# MCU.net
KiCad netlist of a schematic drawn in Altium Designer
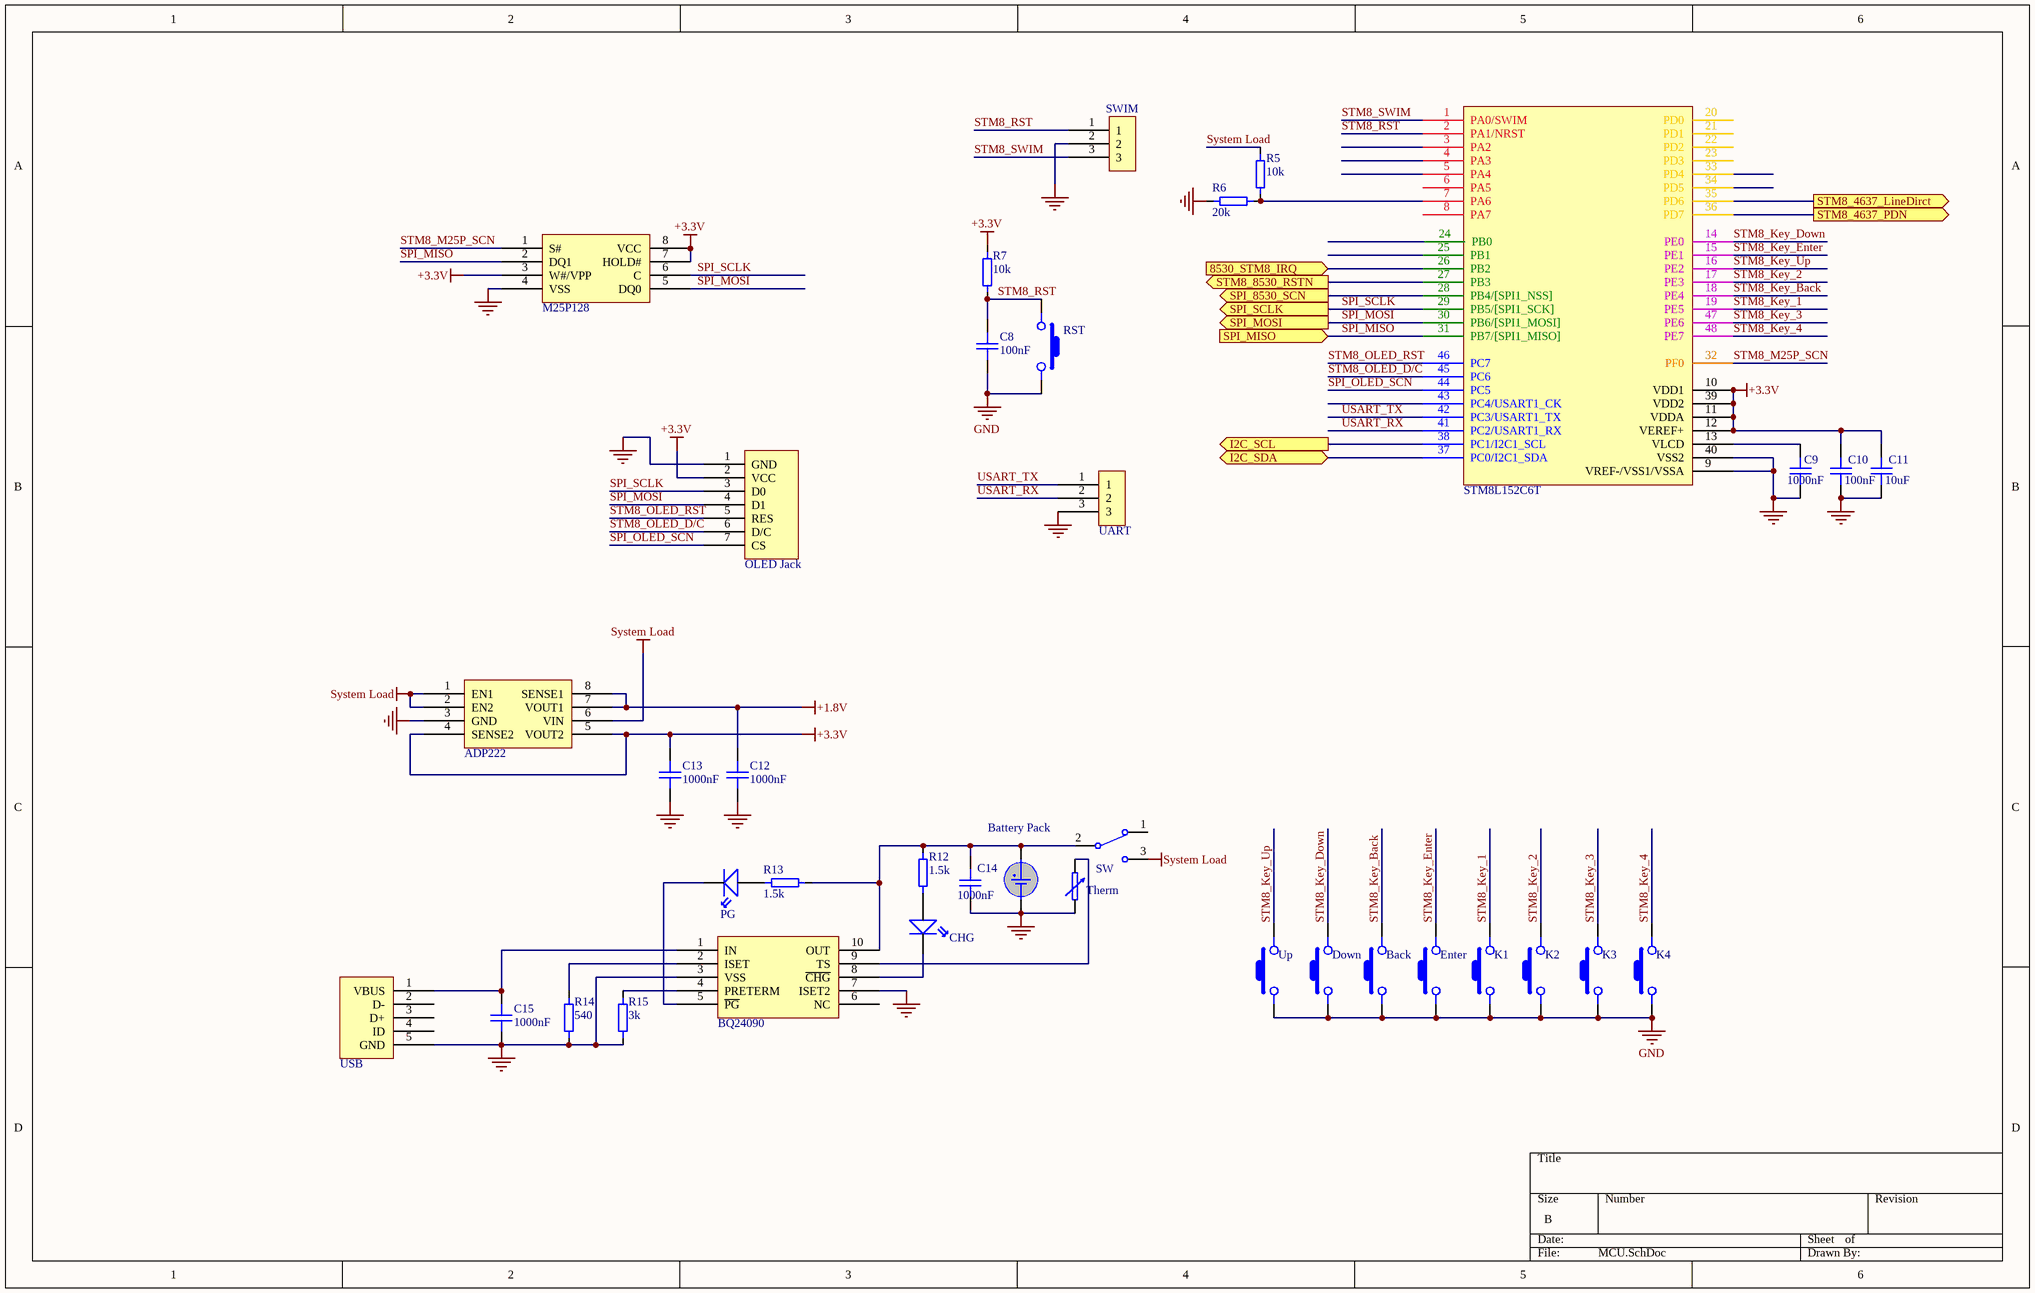
[diagram p0: MCU.SchDoc]

(export (version "E")
  (design (tool "Eeschema 10.0.6"))
  (components
    (comp (ref "ADP222")
      (value "ADP222ACPZ-1833-R7")
      (footprint "ADP22x")
      (libsource (lib "SuperLib") (part "ADP222"))
    )
    (comp (ref "Back") (value "Button") (footprint "Button_3x4") (libsource (lib "WPU161C") (part "Button")))
    (comp (ref "Battery Pack")
      (value "Battery Pack")
      (footprint "Battery Jack small")
      (libsource (lib "SuperLib") (part "Battery Pack"))
    )
    (comp (ref "BQ24090")
      (value "BQ24090")
      (footprint "BQ24090")
      (libsource (lib "WPU161C") (part "BQ24090"))
    )
    (comp (ref "C8")
      (value "100nF")
      (footprint "SMD 0402")
      (fields (field (name "Comment") "Capacity SMD"))
      (libsource (lib "WPU161C") (part "Capacity SMD"))
    )
    (comp (ref "C9")
      (value "1000nF")
      (footprint "SMD 0402")
      (fields (field (name "Comment") "Capacity SMD"))
      (libsource (lib "WPU161C") (part "Capacity SMD"))
    )
    (comp (ref "C10")
      (value "100nF")
      (footprint "SMD 0402")
      (fields (field (name "Comment") "Capacity SMD"))
      (libsource (lib "WPU161C") (part "Capacity SMD"))
    )
    (comp (ref "C11")
      (value "10uF")
      (footprint "SMD 0402")
      (fields (field (name "Comment") "Capacity SMD"))
      (libsource (lib "WPU161C") (part "Capacity SMD"))
    )
    (comp (ref "C12")
      (value "1000nF")
      (footprint "SMD 0402")
      (fields (field (name "Comment") "Capacity SMD"))
      (libsource (lib "WPU161C") (part "Capacity SMD"))
    )
    (comp (ref "C13")
      (value "1000nF")
      (footprint "SMD 0402")
      (fields (field (name "Comment") "Capacity SMD"))
      (libsource (lib "WPU161C") (part "Capacity SMD"))
    )
    (comp (ref "C14")
      (value "1000nF")
      (footprint "SMD 0402")
      (fields (field (name "Comment") "Capacity SMD"))
      (libsource (lib "WPU161C") (part "Capacity SMD"))
    )
    (comp (ref "C15")
      (value "1000nF")
      (footprint "SMD 0402_silk")
      (fields (field (name "Comment") "Capacity SMD"))
      (libsource (lib "WPU161C") (part "Capacity SMD"))
    )
    (comp (ref "CHG") (value "LED") (footprint "LED_0603") (libsource (lib "WPU161C") (part "LED")))
    (comp (ref "Down") (value "Button") (footprint "Button_3x4") (libsource (lib "WPU161C") (part "Button")))
    (comp (ref "Enter") (value "Button") (footprint "Button_3x4") (libsource (lib "WPU161C") (part "Button")))
    (comp (ref "K1") (value "Button") (footprint "Button_3x4") (libsource (lib "WPU161C") (part "Button")))
    (comp (ref "K2") (value "Button") (footprint "Button_3x4") (libsource (lib "WPU161C") (part "Button")))
    (comp (ref "K3") (value "Button") (footprint "Button_3x4") (libsource (lib "WPU161C") (part "Button")))
    (comp (ref "K4") (value "Button") (footprint "Button_3x4") (libsource (lib "WPU161C") (part "Button")))
    (comp (ref "M25P128")
      (value "M25P128")
      (footprint "M25P128")
      (libsource (lib "WPU161C") (part "M25P128"))
    )
    (comp (ref "OLED Jack")
      (value "OLED Jack")
      (footprint "OLED Jack")
      (libsource (lib "WPU161C") (part "OLED Jack"))
    )
    (comp (ref "PG") (value "LED") (footprint "LED_0603") (libsource (lib "WPU161C") (part "LED")))
    (comp (ref "R5")
      (value "10k")
      (footprint "SMD 0402")
      (fields (field (name "Comment") "Resistor SMD"))
      (libsource (lib "WPU161C") (part "Resistor SMD"))
    )
    (comp (ref "R6")
      (value "20k")
      (footprint "SMD 0402")
      (fields (field (name "Comment") "Resistor SMD"))
      (libsource (lib "WPU161C") (part "Resistor SMD"))
    )
    (comp (ref "R7")
      (value "10k")
      (footprint "SMD 0402")
      (fields (field (name "Comment") "Resistor SMD"))
      (libsource (lib "WPU161C") (part "Resistor SMD"))
    )
    (comp (ref "R12")
      (value "1.5k")
      (footprint "SMD 0402")
      (fields (field (name "Comment") "Resistor SMD"))
      (libsource (lib "WPU161C") (part "Resistor SMD"))
    )
    (comp (ref "R13")
      (value "1.5k")
      (footprint "SMD 0402")
      (fields (field (name "Comment") "Resistor SMD"))
      (libsource (lib "WPU161C") (part "Resistor SMD"))
    )
    (comp (ref "R14")
      (value "540")
      (footprint "SMD 0402")
      (fields (field (name "Comment") "Resistor SMD"))
      (libsource (lib "WPU161C") (part "Resistor SMD"))
    )
    (comp (ref "R15")
      (value "3k")
      (footprint "SMD 0402")
      (fields (field (name "Comment") "Resistor SMD"))
      (libsource (lib "WPU161C") (part "Resistor SMD"))
    )
    (comp (ref "RST") (value "Button") (footprint "Button_3x4") (libsource (lib "WPU161C") (part "Button")))
    (comp (ref "STM8L152C6T")
      (value "STM8L152C6T")
      (footprint "STM LQFP48")
      (libsource (lib "WPU161C") (part "STM8L152C6T"))
    )
    (comp (ref "SW") (value "Switch") (footprint "Switch 2P2T") (libsource (lib "WPU161C") (part "Switch")))
    (comp (ref "SWIM")
      (value "Header_3x1")
      (footprint "HEADER_3x1_2.54")
      (libsource (lib "WPU161C") (part "Header_3x1"))
    )
    (comp (ref "Therm")
      (value "Thermistor")
      (footprint "Header_2x1_2.00")
      (libsource (lib "WPU161C") (part "Thermistor NTC"))
    )
    (comp (ref "UART")
      (value "Header_3x1")
      (footprint "HEADER_3x1_2.54")
      (libsource (lib "WPU161C") (part "Header_3x1"))
    )
    (comp (ref "Up") (value "Button") (footprint "Button_3x4") (libsource (lib "WPU161C") (part "Button")))
    (comp (ref "USB")
      (value "USB Jack Mirco-B")
      (footprint "USB Micro-B")
      (libsource (lib "WPU161C") (part "USB Jack Micro-B"))
    )
  )
  (nets
    (net (code "1") (name "+1.8V") (class "Default")
      (node (ref "ADP222") (pin "7") (pinfunction "VOUT1_7") (pintype "passive"))
      (node (ref "ADP222") (pin "8") (pinfunction "SENSE1_8") (pintype "passive"))
      (node (ref "C12") (pin "1") (pintype "passive"))
    )
    (net (code "2") (name "+3.3V") (class "Default")
      (node (ref "ADP222") (pin "4") (pinfunction "SENSE2_4") (pintype "passive"))
      (node (ref "ADP222") (pin "5") (pinfunction "VOUT2_5") (pintype "passive"))
      (node (ref "C10") (pin "2") (pintype "passive"))
      (node (ref "C11") (pin "2") (pintype "passive"))
      (node (ref "C13") (pin "2") (pintype "passive"))
      (node (ref "M25P128") (pin "3") (pinfunction "W#/VPP_3") (pintype "passive"))
      (node (ref "M25P128") (pin "7") (pinfunction "HOLD#_7") (pintype "passive"))
      (node (ref "M25P128") (pin "8") (pinfunction "VCC_8") (pintype "passive"))
      (node (ref "OLED Jack") (pin "2") (pinfunction "VCC_2") (pintype "passive"))
      (node (ref "R7") (pin "2") (pintype "passive"))
      (node (ref "STM8L152C6T") (pin "10") (pinfunction "VDD1_10") (pintype "passive"))
      (node (ref "STM8L152C6T") (pin "11") (pinfunction "VDDA_11") (pintype "passive"))
      (node (ref "STM8L152C6T") (pin "12") (pinfunction "VEREF+_12") (pintype "passive"))
      (node (ref "STM8L152C6T") (pin "39") (pinfunction "VDD2_39") (pintype "passive"))
    )
    (net (code "3") (name "/8530_STM8_IRQ") (class "Default")
      (node (ref "STM8L152C6T") (pin "26") (pinfunction "PB2_26") (pintype "passive"))
    )
    (net (code "4") (name "/I2C_SCL") (class "Default")
      (node (ref "STM8L152C6T") (pin "38") (pinfunction "PC1/I2C1_SCL_38") (pintype "passive"))
    )
    (net (code "5") (name "/I2C_SDA") (class "Default")
      (node (ref "STM8L152C6T") (pin "37") (pinfunction "PC0/I2C1_SDA_37") (pintype "passive"))
    )
    (net (code "6") (name "/SPI_8530_SCN") (class "Default")
      (node (ref "STM8L152C6T") (pin "28") (pinfunction "PB4/[SPI1_NSS]_28") (pintype "passive"))
    )
    (net (code "7") (name "/SPI_MISO") (class "Default")
      (node (ref "M25P128") (pin "2") (pinfunction "DQ1_2") (pintype "passive"))
      (node (ref "STM8L152C6T") (pin "31") (pinfunction "PB7/[SPI1_MISO]_31") (pintype "passive"))
    )
    (net (code "8") (name "/SPI_MOSI") (class "Default")
      (node (ref "M25P128") (pin "5") (pinfunction "DQ0_5") (pintype "passive"))
      (node (ref "OLED Jack") (pin "4") (pinfunction "D1_4") (pintype "passive"))
      (node (ref "STM8L152C6T") (pin "30") (pinfunction "PB6/[SPI1_MOSI]_30") (pintype "passive"))
    )
    (net (code "9") (name "/SPI_OLED_SCN") (class "Default")
      (node (ref "OLED Jack") (pin "7") (pinfunction "CS_7") (pintype "passive"))
      (node (ref "STM8L152C6T") (pin "44") (pinfunction "PC5_44") (pintype "passive"))
    )
    (net (code "10") (name "/SPI_SCLK") (class "Default")
      (node (ref "M25P128") (pin "6") (pinfunction "C_6") (pintype "passive"))
      (node (ref "OLED Jack") (pin "3") (pinfunction "D0_3") (pintype "passive"))
      (node (ref "STM8L152C6T") (pin "29") (pinfunction "PB5/[SPI1_SCK]_29") (pintype "passive"))
    )
    (net (code "11") (name "/STM8_4637_LineDirct") (class "Default")
      (node (ref "STM8L152C6T") (pin "35") (pinfunction "PD6_35") (pintype "passive"))
    )
    (net (code "12") (name "/STM8_4637_PDN") (class "Default")
      (node (ref "STM8L152C6T") (pin "36") (pinfunction "PD7_36") (pintype "passive"))
    )
    (net (code "13") (name "/STM8_8530_RSTN") (class "Default")
      (node (ref "STM8L152C6T") (pin "27") (pinfunction "PB3_27") (pintype "passive"))
    )
    (net (code "14") (name "/STM8_Key_1") (class "Default")
      (node (ref "K1") (pin "1") (pintype "passive"))
      (node (ref "STM8L152C6T") (pin "19") (pinfunction "PE5_19") (pintype "passive"))
    )
    (net (code "15") (name "/STM8_Key_2") (class "Default")
      (node (ref "K2") (pin "1") (pintype "passive"))
      (node (ref "STM8L152C6T") (pin "17") (pinfunction "PE3_17") (pintype "passive"))
    )
    (net (code "16") (name "/STM8_Key_3") (class "Default")
      (node (ref "K3") (pin "1") (pintype "passive"))
      (node (ref "STM8L152C6T") (pin "47") (pinfunction "PE6_47") (pintype "passive"))
    )
    (net (code "17") (name "/STM8_Key_4") (class "Default")
      (node (ref "K4") (pin "1") (pintype "passive"))
      (node (ref "STM8L152C6T") (pin "48") (pinfunction "PE7_48") (pintype "passive"))
    )
    (net (code "18") (name "/STM8_Key_Back") (class "Default")
      (node (ref "Back") (pin "1") (pintype "passive"))
      (node (ref "STM8L152C6T") (pin "18") (pinfunction "PE4_18") (pintype "passive"))
    )
    (net (code "19") (name "/STM8_Key_Down") (class "Default")
      (node (ref "Down") (pin "1") (pintype "passive"))
      (node (ref "STM8L152C6T") (pin "14") (pinfunction "PE0_14") (pintype "passive"))
    )
    (net (code "20") (name "/STM8_Key_Enter") (class "Default")
      (node (ref "Enter") (pin "1") (pintype "passive"))
      (node (ref "STM8L152C6T") (pin "15") (pinfunction "PE1_15") (pintype "passive"))
    )
    (net (code "21") (name "/STM8_Key_Up") (class "Default")
      (node (ref "STM8L152C6T") (pin "16") (pinfunction "PE2_16") (pintype "passive"))
      (node (ref "Up") (pin "1") (pintype "passive"))
    )
    (net (code "22") (name "/STM8_M25P_SCN") (class "Default")
      (node (ref "M25P128") (pin "1") (pinfunction "S#_1") (pintype "passive"))
      (node (ref "STM8L152C6T") (pin "32") (pinfunction "PF0_32") (pintype "passive"))
    )
    (net (code "23") (name "/STM8_OLED_D{slash}C") (class "Default")
      (node (ref "OLED Jack") (pin "6") (pinfunction "D/C_6") (pintype "passive"))
      (node (ref "STM8L152C6T") (pin "45") (pinfunction "PC6_45") (pintype "passive"))
    )
    (net (code "24") (name "/STM8_OLED_RST") (class "Default")
      (node (ref "OLED Jack") (pin "5") (pinfunction "RES_5") (pintype "passive"))
      (node (ref "STM8L152C6T") (pin "46") (pinfunction "PC7_46") (pintype "passive"))
    )
    (net (code "25") (name "/STM8_RST") (class "Default")
      (node (ref "C8") (pin "2") (pintype "passive"))
      (node (ref "R7") (pin "1") (pintype "passive"))
      (node (ref "RST") (pin "2") (pintype "passive"))
      (node (ref "STM8L152C6T") (pin "2") (pinfunction "PA1/NRST_2") (pintype "passive"))
      (node (ref "SWIM") (pin "1") (pinfunction "1_1") (pintype "passive"))
    )
    (net (code "26") (name "/STM8_SWIM") (class "Default")
      (node (ref "STM8L152C6T") (pin "1") (pinfunction "PA0/SWIM_1") (pintype "passive"))
      (node (ref "SWIM") (pin "3") (pinfunction "3_3") (pintype "passive"))
    )
    (net (code "27") (name "/USART_RX") (class "Default")
      (node (ref "STM8L152C6T") (pin "41") (pinfunction "PC2/USART1_RX_41") (pintype "passive"))
      (node (ref "UART") (pin "2") (pinfunction "2_2") (pintype "passive"))
    )
    (net (code "28") (name "/USART_TX") (class "Default")
      (node (ref "STM8L152C6T") (pin "42") (pinfunction "PC3/USART1_TX_42") (pintype "passive"))
      (node (ref "UART") (pin "1") (pinfunction "1_1") (pintype "passive"))
    )
    (net (code "29") (name "GND") (class "Default")
      (node (ref "ADP222") (pin "3") (pinfunction "GND_3") (pintype "passive"))
      (node (ref "BQ24090") (pin "3") (pinfunction "VSS_3") (pintype "passive"))
      (node (ref "BQ24090") (pin "7") (pinfunction "ISET2_7") (pintype "passive"))
      (node (ref "Back") (pin "2") (pintype "passive"))
      (node (ref "Battery Pack") (pin "2") (pinfunction "2_2") (pintype "passive"))
      (node (ref "C10") (pin "1") (pintype "passive"))
      (node (ref "C11") (pin "1") (pintype "passive"))
      (node (ref "C12") (pin "2") (pintype "passive"))
      (node (ref "C13") (pin "1") (pintype "passive"))
      (node (ref "C14") (pin "1") (pintype "passive"))
      (node (ref "C15") (pin "1") (pintype "passive"))
      (node (ref "C8") (pin "1") (pintype "passive"))
      (node (ref "C9") (pin "1") (pintype "passive"))
      (node (ref "Down") (pin "2") (pintype "passive"))
      (node (ref "Enter") (pin "2") (pintype "passive"))
      (node (ref "K1") (pin "2") (pintype "passive"))
      (node (ref "K2") (pin "2") (pintype "passive"))
      (node (ref "K3") (pin "2") (pintype "passive"))
      (node (ref "K4") (pin "2") (pintype "passive"))
      (node (ref "M25P128") (pin "4") (pinfunction "VSS_4") (pintype "passive"))
      (node (ref "OLED Jack") (pin "1") (pinfunction "GND_1") (pintype "passive"))
      (node (ref "R14") (pin "1") (pintype "passive"))
      (node (ref "R15") (pin "1") (pintype "passive"))
      (node (ref "R6") (pin "1") (pintype "passive"))
      (node (ref "RST") (pin "1") (pintype "passive"))
      (node (ref "STM8L152C6T") (pin "40") (pinfunction "VSS2_40") (pintype "passive"))
      (node (ref "STM8L152C6T") (pin "9") (pinfunction "VREF-/VSS1/VSSA_9") (pintype "passive"))
      (node (ref "SWIM") (pin "2") (pinfunction "2_2") (pintype "passive"))
      (node (ref "Therm") (pin "2") (pinfunction "2_2") (pintype "passive"))
      (node (ref "UART") (pin "3") (pinfunction "3_3") (pintype "passive"))
      (node (ref "USB") (pin "5") (pinfunction "GND_5") (pintype "passive"))
      (node (ref "Up") (pin "2") (pintype "passive"))
    )
    (net (code "30") (name "Net-(BQ24090-IN)") (class "Default")
      (node (ref "BQ24090") (pin "1") (pinfunction "IN_1") (pintype "passive"))
      (node (ref "C15") (pin "2") (pintype "passive"))
      (node (ref "USB") (pin "1") (pinfunction "VBUS_1") (pintype "passive"))
    )
    (net (code "31") (name "Net-(BQ24090-ISET)") (class "Default")
      (node (ref "BQ24090") (pin "2") (pinfunction "ISET_2") (pintype "passive"))
      (node (ref "R14") (pin "2") (pintype "passive"))
    )
    (net (code "32") (name "Net-(BQ24090-OUT)") (class "Default")
      (node (ref "BQ24090") (pin "10") (pinfunction "OUT_10") (pintype "passive"))
      (node (ref "Battery Pack") (pin "1") (pinfunction "1_1") (pintype "passive"))
      (node (ref "C14") (pin "2") (pintype "passive"))
      (node (ref "R12") (pin "2") (pintype "passive"))
      (node (ref "R13") (pin "2") (pintype "passive"))
      (node (ref "SW") (pin "2") (pintype "passive"))
    )
    (net (code "33") (name "Net-(BQ24090-PRETERM)") (class "Default")
      (node (ref "BQ24090") (pin "4") (pinfunction "PRETERM_4") (pintype "passive"))
      (node (ref "R15") (pin "2") (pintype "passive"))
    )
    (net (code "34") (name "Net-(BQ24090-TS)") (class "Default")
      (node (ref "BQ24090") (pin "9") (pinfunction "TS_9") (pintype "passive"))
      (node (ref "Therm") (pin "1") (pinfunction "1_1") (pintype "passive"))
    )
    (net (code "35") (name "Net-(BQ24090-~{CHG})") (class "Default")
      (node (ref "BQ24090") (pin "8") (pinfunction "~{CHG}_8") (pintype "passive"))
      (node (ref "CHG") (pin "2") (pinfunction "2_2") (pintype "passive"))
    )
    (net (code "36") (name "Net-(BQ24090-~{PG})") (class "Default")
      (node (ref "BQ24090") (pin "5") (pinfunction "~{PG}_5") (pintype "passive"))
      (node (ref "PG") (pin "2") (pinfunction "2_2") (pintype "passive"))
    )
    (net (code "37") (name "Net-(CHG-Pad1)") (class "Default")
      (node (ref "CHG") (pin "1") (pinfunction "1_1") (pintype "passive"))
      (node (ref "R12") (pin "1") (pintype "passive"))
    )
    (net (code "38") (name "Net-(PG-Pad1)") (class "Default")
      (node (ref "PG") (pin "1") (pinfunction "1_1") (pintype "passive"))
      (node (ref "R13") (pin "1") (pintype "passive"))
    )
    (net (code "39") (name "Net-(STM8L152C6T-PA6)") (class "Default")
      (node (ref "R5") (pin "1") (pintype "passive"))
      (node (ref "R6") (pin "2") (pintype "passive"))
      (node (ref "STM8L152C6T") (pin "7") (pinfunction "PA6_7") (pintype "passive"))
    )
    (net (code "40") (name "Net-(STM8L152C6T-VLCD)") (class "Default")
      (node (ref "C9") (pin "2") (pintype "passive"))
      (node (ref "STM8L152C6T") (pin "13") (pinfunction "VLCD_13") (pintype "passive"))
    )
    (net (code "41") (name "System Load") (class "Default")
      (node (ref "ADP222") (pin "1") (pinfunction "EN1_1") (pintype "passive"))
      (node (ref "ADP222") (pin "2") (pinfunction "EN2_2") (pintype "passive"))
      (node (ref "ADP222") (pin "6") (pinfunction "VIN_6") (pintype "passive"))
      (node (ref "R5") (pin "2") (pintype "passive"))
      (node (ref "SW") (pin "3") (pintype "passive"))
    )
    (net (code "42") (name "unconnected-(BQ24090-NC-Pad6)") (class "Default")
      (node (ref "BQ24090") (pin "6") (pinfunction "NC_6") (pintype "passive"))
    )
    (net (code "43") (name "unconnected-(STM8L152C6T-PA2-Pad3)") (class "Default")
      (node (ref "STM8L152C6T") (pin "3") (pinfunction "PA2_3") (pintype "passive"))
    )
    (net (code "44") (name "unconnected-(STM8L152C6T-PA3-Pad4)") (class "Default")
      (node (ref "STM8L152C6T") (pin "4") (pinfunction "PA3_4") (pintype "passive"))
    )
    (net (code "45") (name "unconnected-(STM8L152C6T-PA4-Pad5)") (class "Default")
      (node (ref "STM8L152C6T") (pin "5") (pinfunction "PA4_5") (pintype "passive"))
    )
    (net (code "46") (name "unconnected-(STM8L152C6T-PA5-Pad6)") (class "Default")
      (node (ref "STM8L152C6T") (pin "6") (pinfunction "PA5_6") (pintype "passive"))
    )
    (net (code "47") (name "unconnected-(STM8L152C6T-PA7-Pad8)") (class "Default")
      (node (ref "STM8L152C6T") (pin "8") (pinfunction "PA7_8") (pintype "passive"))
    )
    (net (code "48") (name "unconnected-(STM8L152C6T-PB0-Pad24)") (class "Default")
      (node (ref "STM8L152C6T") (pin "24") (pinfunction "PB0_24") (pintype "passive"))
    )
    (net (code "49") (name "unconnected-(STM8L152C6T-PB1-Pad25)") (class "Default")
      (node (ref "STM8L152C6T") (pin "25") (pinfunction "PB1_25") (pintype "passive"))
    )
    (net (code "50") (name "unconnected-(STM8L152C6T-PC4{slash}USART1_CK-Pad43)") (class "Default")
      (node (ref "STM8L152C6T") (pin "43") (pinfunction "PC4/USART1_CK_43") (pintype "passive"))
    )
    (net (code "51") (name "unconnected-(STM8L152C6T-PD0-Pad20)") (class "Default")
      (node (ref "STM8L152C6T") (pin "20") (pinfunction "PD0_20") (pintype "passive"))
    )
    (net (code "52") (name "unconnected-(STM8L152C6T-PD1-Pad21)") (class "Default")
      (node (ref "STM8L152C6T") (pin "21") (pinfunction "PD1_21") (pintype "passive"))
    )
    (net (code "53") (name "unconnected-(STM8L152C6T-PD2-Pad22)") (class "Default")
      (node (ref "STM8L152C6T") (pin "22") (pinfunction "PD2_22") (pintype "passive"))
    )
    (net (code "54") (name "unconnected-(STM8L152C6T-PD3-Pad23)") (class "Default")
      (node (ref "STM8L152C6T") (pin "23") (pinfunction "PD3_23") (pintype "passive"))
    )
    (net (code "55") (name "unconnected-(STM8L152C6T-PD4-Pad33)") (class "Default")
      (node (ref "STM8L152C6T") (pin "33") (pinfunction "PD4_33") (pintype "passive"))
    )
    (net (code "56") (name "unconnected-(STM8L152C6T-PD5-Pad34)") (class "Default")
      (node (ref "STM8L152C6T") (pin "34") (pinfunction "PD5_34") (pintype "passive"))
    )
    (net (code "57") (name "unconnected-(SW-Pad1)") (class "Default")
      (node (ref "SW") (pin "1") (pintype "passive"))
    )
    (net (code "58") (name "unconnected-(USB-D+-Pad3)") (class "Default")
      (node (ref "USB") (pin "3") (pinfunction "D+_3") (pintype "passive"))
    )
    (net (code "59") (name "unconnected-(USB-D--Pad2)") (class "Default")
      (node (ref "USB") (pin "2") (pinfunction "D-_2") (pintype "passive"))
    )
    (net (code "60") (name "unconnected-(USB-ID-Pad4)") (class "Default")
      (node (ref "USB") (pin "4") (pinfunction "ID_4") (pintype "passive"))
    )
  )
)
